# QRD1114-bar.net
KiCad netlist of a schematic drawn in EAGLE
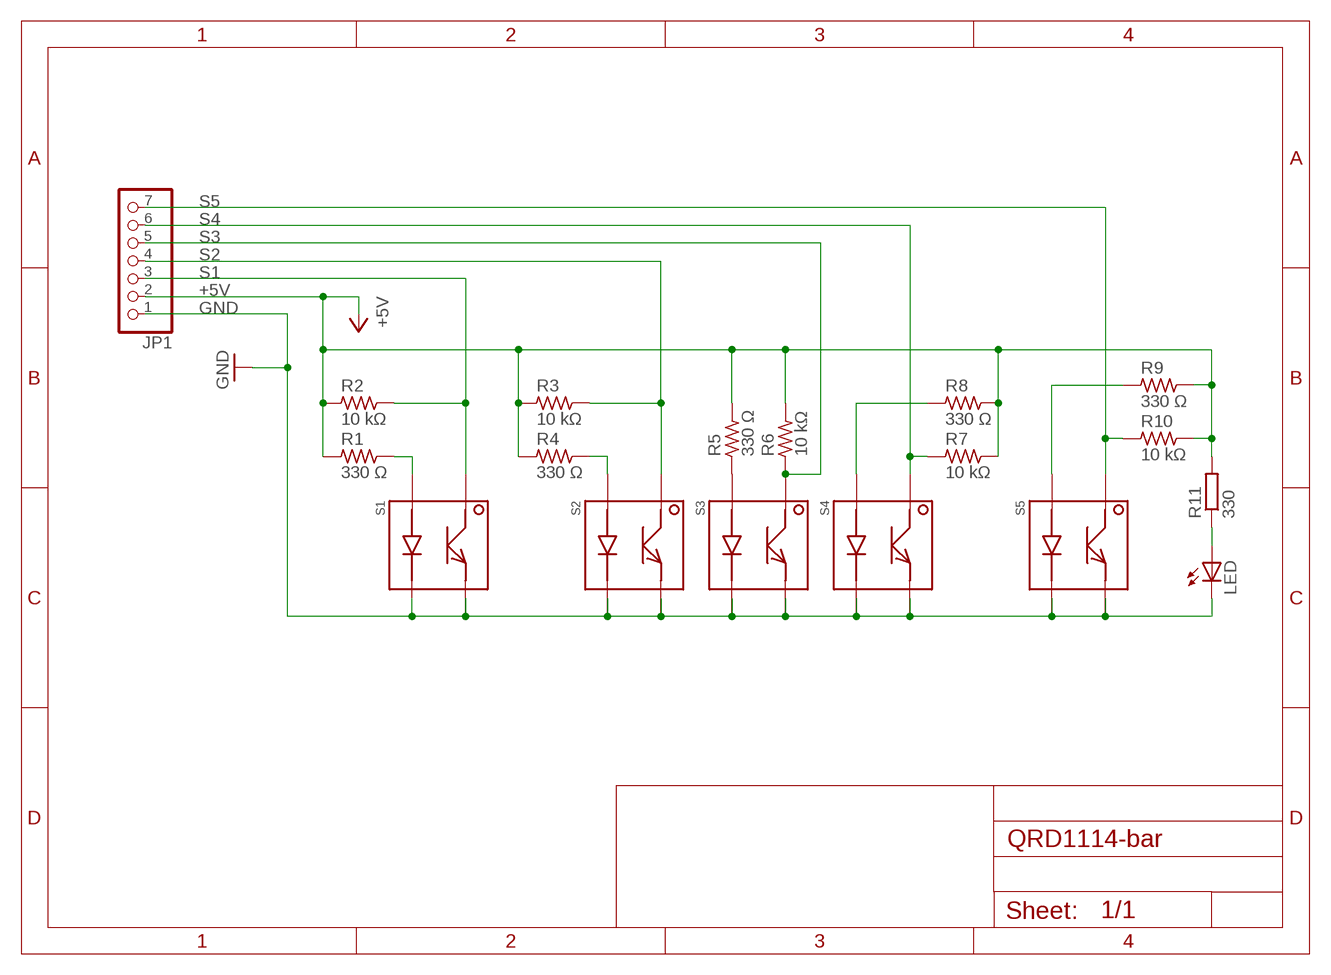
[diagram p0: schematic, sheet 1]

(export (version "E")
  (design (tool "Eeschema 10.0.6"))
  (components
    (comp (ref "JP1")
      (value "PINHD-1X7")
      (footprint "eagle-import:1X07")
      (libsource (lib "eagle-import") (part "PINHD-1X7"))
    )
    (comp (ref "LED")
      (value "LEDSML0805")
      (footprint "eagle-import:SML0805")
      (libsource (lib "eagle-import") (part "LEDSML0805"))
    )
    (comp (ref "R1")
      (value "330 Ω")
      (footprint "eagle-import:R0603")
      (fields (field (name "MF") "VISHAY") (field (name "MPN") "CRCW0805330RFKEA"))
      (libsource (lib "eagle-import") (part "R_0603"))
    )
    (comp (ref "R2")
      (value "10 kΩ")
      (footprint "eagle-import:R0603")
      (libsource (lib "eagle-import") (part "R_0603"))
    )
    (comp (ref "R3")
      (value "10 kΩ")
      (footprint "eagle-import:R0603")
      (libsource (lib "eagle-import") (part "R_0603"))
    )
    (comp (ref "R4")
      (value "330 Ω")
      (footprint "eagle-import:R0603")
      (fields (field (name "MF") "VISHAY") (field (name "MPN") "CRCW0805330RFKEA"))
      (libsource (lib "eagle-import") (part "R_0603"))
    )
    (comp (ref "R5")
      (value "330 Ω")
      (footprint "eagle-import:R0603")
      (fields (field (name "MF") "VISHAY") (field (name "MPN") "CRCW0805330RFKEA"))
      (libsource (lib "eagle-import") (part "R_0603"))
    )
    (comp (ref "R6")
      (value "10 kΩ")
      (footprint "eagle-import:R0603")
      (libsource (lib "eagle-import") (part "R_0603"))
    )
    (comp (ref "R7")
      (value "10 kΩ")
      (footprint "eagle-import:R0603")
      (libsource (lib "eagle-import") (part "R_0603"))
    )
    (comp (ref "R8")
      (value "330 Ω")
      (footprint "eagle-import:R0603")
      (fields (field (name "MF") "VISHAY") (field (name "MPN") "CRCW0805330RFKEA"))
      (libsource (lib "eagle-import") (part "R_0603"))
    )
    (comp (ref "R9")
      (value "330 Ω")
      (footprint "eagle-import:R0603")
      (fields (field (name "MF") "VISHAY") (field (name "MPN") "CRCW0805330RFKEA"))
      (libsource (lib "eagle-import") (part "R_0603"))
    )
    (comp (ref "R10")
      (value "10 kΩ")
      (footprint "eagle-import:R0603")
      (libsource (lib "eagle-import") (part "R_0603"))
    )
    (comp (ref "R11")
      (value "330")
      (footprint "eagle-import:R0603")
      (libsource (lib "eagle-import") (part "R-EU_R0603"))
    )
    (comp (ref "S1")
      (value "QRD1114")
      (footprint "eagle-import:QRD1114")
      (fields (field (name "MF") "ON Semiconductor") (field (name "MF_1") "ON SEMICONDUCTOR"))
      (libsource (lib "eagle-import") (part "QRD1114"))
    )
    (comp (ref "S2")
      (value "QRD1114")
      (footprint "eagle-import:QRD1114")
      (fields (field (name "MF") "ON Semiconductor") (field (name "MF_1") "ON SEMICONDUCTOR"))
      (libsource (lib "eagle-import") (part "QRD1114"))
    )
    (comp (ref "S3")
      (value "QRD1114")
      (footprint "eagle-import:QRD1114")
      (fields (field (name "MF") "ON Semiconductor") (field (name "MF_1") "ON SEMICONDUCTOR"))
      (libsource (lib "eagle-import") (part "QRD1114"))
    )
    (comp (ref "S4")
      (value "QRD1114")
      (footprint "eagle-import:QRD1114")
      (fields (field (name "MF") "ON Semiconductor") (field (name "MF_1") "ON SEMICONDUCTOR"))
      (libsource (lib "eagle-import") (part "QRD1114"))
    )
    (comp (ref "S5")
      (value "QRD1114")
      (footprint "eagle-import:QRD1114")
      (fields (field (name "MF") "ON Semiconductor"))
      (libsource (lib "eagle-import") (part "QRD1114"))
    )
  )
  (nets
    (net (code "1") (name "+5V") (class "Default")
      (node (ref "JP1") (pin "2") (pinfunction "2_2") (pintype "passive"))
      (node (ref "R1") (pin "1") (pinfunction "1_1") (pintype "passive"))
      (node (ref "R10") (pin "2") (pinfunction "2_2") (pintype "passive"))
      (node (ref "R11") (pin "2") (pinfunction "2_2") (pintype "passive"))
      (node (ref "R2") (pin "1") (pinfunction "1_1") (pintype "passive"))
      (node (ref "R3") (pin "1") (pinfunction "1_1") (pintype "passive"))
      (node (ref "R4") (pin "1") (pinfunction "1_1") (pintype "passive"))
      (node (ref "R5") (pin "2") (pinfunction "2_2") (pintype "passive"))
      (node (ref "R6") (pin "2") (pinfunction "2_2") (pintype "passive"))
      (node (ref "R7") (pin "2") (pinfunction "2_2") (pintype "passive"))
      (node (ref "R8") (pin "2") (pinfunction "2_2") (pintype "passive"))
      (node (ref "R9") (pin "2") (pinfunction "2_2") (pintype "passive"))
    )
    (net (code "2") (name "/S1") (class "Default")
      (node (ref "JP1") (pin "3") (pinfunction "3_3") (pintype "passive"))
      (node (ref "R2") (pin "2") (pinfunction "2_2") (pintype "passive"))
      (node (ref "S1") (pin "P$1") (pinfunction "P$1_P$1") (pintype "bidirectional"))
    )
    (net (code "3") (name "/S2") (class "Default")
      (node (ref "JP1") (pin "4") (pinfunction "4_4") (pintype "passive"))
      (node (ref "R3") (pin "2") (pinfunction "2_2") (pintype "passive"))
      (node (ref "S2") (pin "P$1") (pinfunction "P$1_P$1") (pintype "bidirectional"))
    )
    (net (code "4") (name "/S3") (class "Default")
      (node (ref "JP1") (pin "5") (pinfunction "5_5") (pintype "passive"))
      (node (ref "R6") (pin "1") (pinfunction "1_1") (pintype "passive"))
      (node (ref "S3") (pin "P$1") (pinfunction "P$1_P$1") (pintype "bidirectional"))
    )
    (net (code "5") (name "/S4") (class "Default")
      (node (ref "JP1") (pin "6") (pinfunction "6_6") (pintype "passive"))
      (node (ref "R7") (pin "1") (pinfunction "1_1") (pintype "passive"))
      (node (ref "S4") (pin "P$1") (pinfunction "P$1_P$1") (pintype "bidirectional"))
    )
    (net (code "6") (name "/S5") (class "Default")
      (node (ref "JP1") (pin "7") (pinfunction "7_7") (pintype "passive"))
      (node (ref "R10") (pin "1") (pinfunction "1_1") (pintype "passive"))
      (node (ref "S5") (pin "P$1") (pinfunction "P$1_P$1") (pintype "bidirectional"))
    )
    (net (code "7") (name "GND") (class "Default")
      (node (ref "JP1") (pin "1") (pinfunction "1_1") (pintype "passive"))
      (node (ref "LED") (pin "C") (pinfunction "C_C") (pintype "passive"))
      (node (ref "S1") (pin "P$2") (pinfunction "P$2_P$2") (pintype "bidirectional"))
      (node (ref "S1") (pin "P$4") (pinfunction "P$4_P$4") (pintype "bidirectional"))
      (node (ref "S2") (pin "P$2") (pinfunction "P$2_P$2") (pintype "bidirectional"))
      (node (ref "S2") (pin "P$4") (pinfunction "P$4_P$4") (pintype "bidirectional"))
      (node (ref "S3") (pin "P$2") (pinfunction "P$2_P$2") (pintype "bidirectional"))
      (node (ref "S3") (pin "P$4") (pinfunction "P$4_P$4") (pintype "bidirectional"))
      (node (ref "S4") (pin "P$2") (pinfunction "P$2_P$2") (pintype "bidirectional"))
      (node (ref "S4") (pin "P$4") (pinfunction "P$4_P$4") (pintype "bidirectional"))
      (node (ref "S5") (pin "P$2") (pinfunction "P$2_P$2") (pintype "bidirectional"))
      (node (ref "S5") (pin "P$4") (pinfunction "P$4_P$4") (pintype "bidirectional"))
    )
    (net (code "8") (name "Net-(LED-PadA)") (class "Default")
      (node (ref "LED") (pin "A") (pinfunction "A_A") (pintype "passive"))
      (node (ref "R11") (pin "1") (pinfunction "1_1") (pintype "passive"))
    )
    (net (code "9") (name "Net-(R1-Pad2)") (class "Default")
      (node (ref "R1") (pin "2") (pinfunction "2_2") (pintype "passive"))
      (node (ref "S1") (pin "P$3") (pinfunction "P$3_P$3") (pintype "bidirectional"))
    )
    (net (code "10") (name "Net-(R4-Pad2)") (class "Default")
      (node (ref "R4") (pin "2") (pinfunction "2_2") (pintype "passive"))
      (node (ref "S2") (pin "P$3") (pinfunction "P$3_P$3") (pintype "bidirectional"))
    )
    (net (code "11") (name "Net-(R5-Pad1)") (class "Default")
      (node (ref "R5") (pin "1") (pinfunction "1_1") (pintype "passive"))
      (node (ref "S3") (pin "P$3") (pinfunction "P$3_P$3") (pintype "bidirectional"))
    )
    (net (code "12") (name "Net-(R8-Pad1)") (class "Default")
      (node (ref "R8") (pin "1") (pinfunction "1_1") (pintype "passive"))
      (node (ref "S4") (pin "P$3") (pinfunction "P$3_P$3") (pintype "bidirectional"))
    )
    (net (code "13") (name "Net-(R9-Pad1)") (class "Default")
      (node (ref "R9") (pin "1") (pinfunction "1_1") (pintype "passive"))
      (node (ref "S5") (pin "P$3") (pinfunction "P$3_P$3") (pintype "bidirectional"))
    )
  )
)
